# MPU-6050_Shield.net
KiCad netlist of a schematic drawn in EAGLE
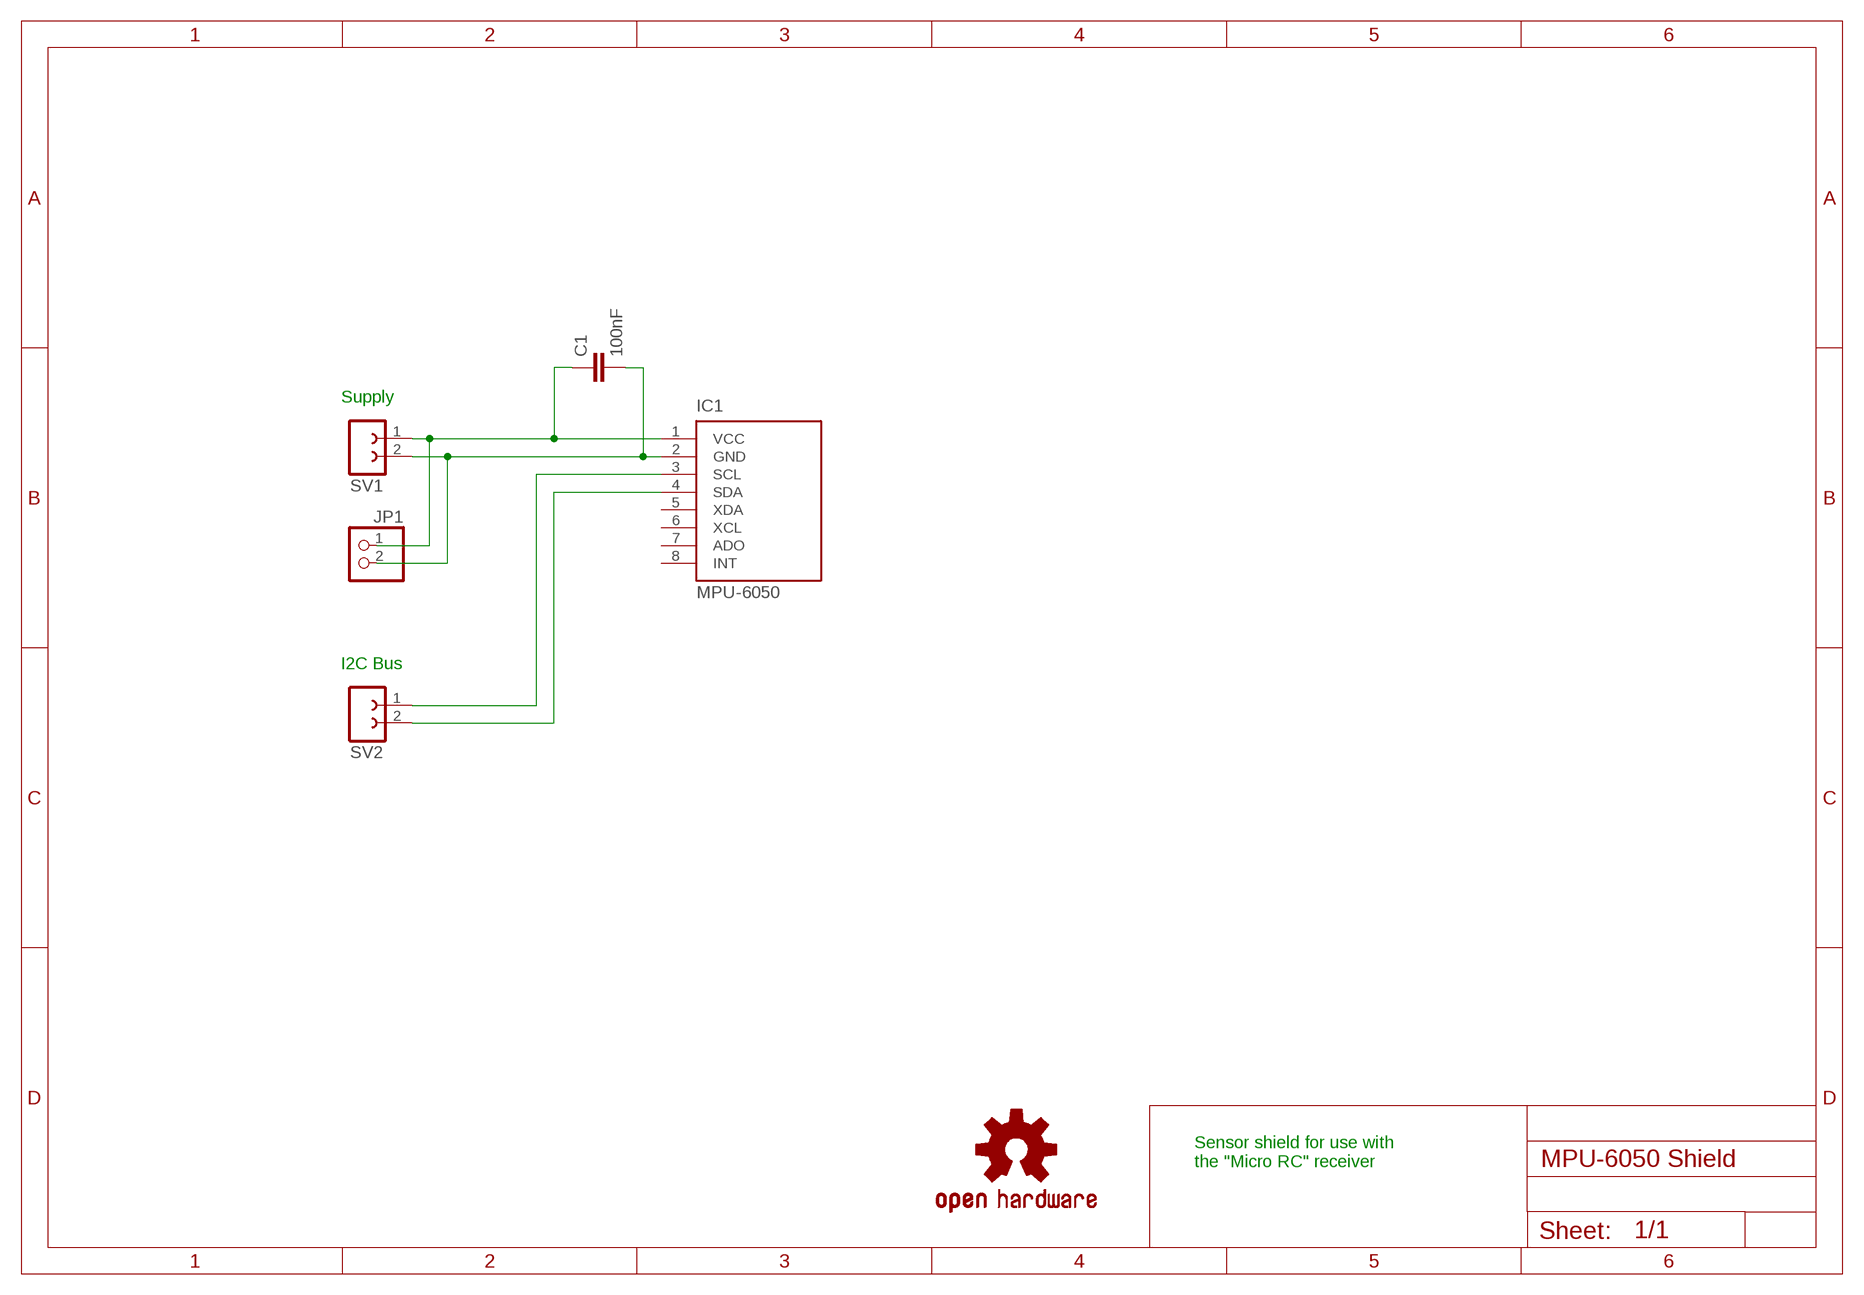
[diagram p0: schematic, sheet 1]

(export (version "E")
  (design (tool "Eeschema 10.0.6"))
  (components
    (comp (ref "C1")
      (value "100nF")
      (footprint "eagle-import:C0805")
      (libsource (lib "eagle-import") (part "C-EUC0805"))
    )
    (comp (ref "IC1")
      (value "MPU-6050")
      (footprint "eagle-import:MPU-6050_GY521")
      (libsource (lib "eagle-import") (part "MPU-6050"))
    )
    (comp (ref "JP1")
      (value "PINHD-1X2")
      (footprint "eagle-import:1X02")
      (libsource (lib "eagle-import") (part "PINHD-1X2"))
    )
    (comp (ref "LOGO1")
      (value "OSHW-LOGOS")
      (footprint "eagle-import:OSHW-LOGO-S")
      (libsource (lib "eagle-import") (part "OSHW-LOGOS"))
    )
    (comp (ref "SV1")
      (value "FE02-1")
      (footprint "eagle-import:FE02-1")
      (libsource (lib "eagle-import") (part "FE02-1"))
    )
    (comp (ref "SV2")
      (value "FE02-1")
      (footprint "eagle-import:FE02-1")
      (libsource (lib "eagle-import") (part "FE02-1"))
    )
  )
  (nets
    (net (code "1") (name "Net-(IC1-GND)") (class "Default")
      (node (ref "C1") (pin "2") (pinfunction "2_2") (pintype "passive"))
      (node (ref "IC1") (pin "2") (pinfunction "GND_2") (pintype "bidirectional"))
      (node (ref "JP1") (pin "2") (pinfunction "2_2") (pintype "passive"))
      (node (ref "SV1") (pin "2") (pinfunction "2_2") (pintype "passive"))
    )
    (net (code "2") (name "Net-(IC1-SCL)") (class "Default")
      (node (ref "IC1") (pin "3") (pinfunction "SCL_3") (pintype "bidirectional"))
      (node (ref "SV2") (pin "1") (pinfunction "1_1") (pintype "passive"))
    )
    (net (code "3") (name "Net-(IC1-SDA)") (class "Default")
      (node (ref "IC1") (pin "4") (pinfunction "SDA_4") (pintype "bidirectional"))
      (node (ref "SV2") (pin "2") (pinfunction "2_2") (pintype "passive"))
    )
    (net (code "4") (name "Net-(IC1-VCC)") (class "Default")
      (node (ref "C1") (pin "1") (pinfunction "1_1") (pintype "passive"))
      (node (ref "IC1") (pin "1") (pinfunction "VCC_1") (pintype "bidirectional"))
      (node (ref "JP1") (pin "1") (pinfunction "1_1") (pintype "passive"))
      (node (ref "SV1") (pin "1") (pinfunction "1_1") (pintype "passive"))
    )
    (net (code "5") (name "unconnected-(IC1-ADO-Pad7)") (class "Default")
      (node (ref "IC1") (pin "7") (pinfunction "ADO_7") (pintype "bidirectional"))
    )
    (net (code "6") (name "unconnected-(IC1-INT-Pad8)") (class "Default")
      (node (ref "IC1") (pin "8") (pinfunction "INT_8") (pintype "bidirectional"))
    )
    (net (code "7") (name "unconnected-(IC1-XCL-Pad6)") (class "Default")
      (node (ref "IC1") (pin "6") (pinfunction "XCL_6") (pintype "bidirectional"))
    )
    (net (code "8") (name "unconnected-(IC1-XDA-Pad5)") (class "Default")
      (node (ref "IC1") (pin "5") (pinfunction "XDA_5") (pintype "bidirectional"))
    )
  )
)
